# M-Fader.net
KiCad netlist of a schematic drawn in EAGLE
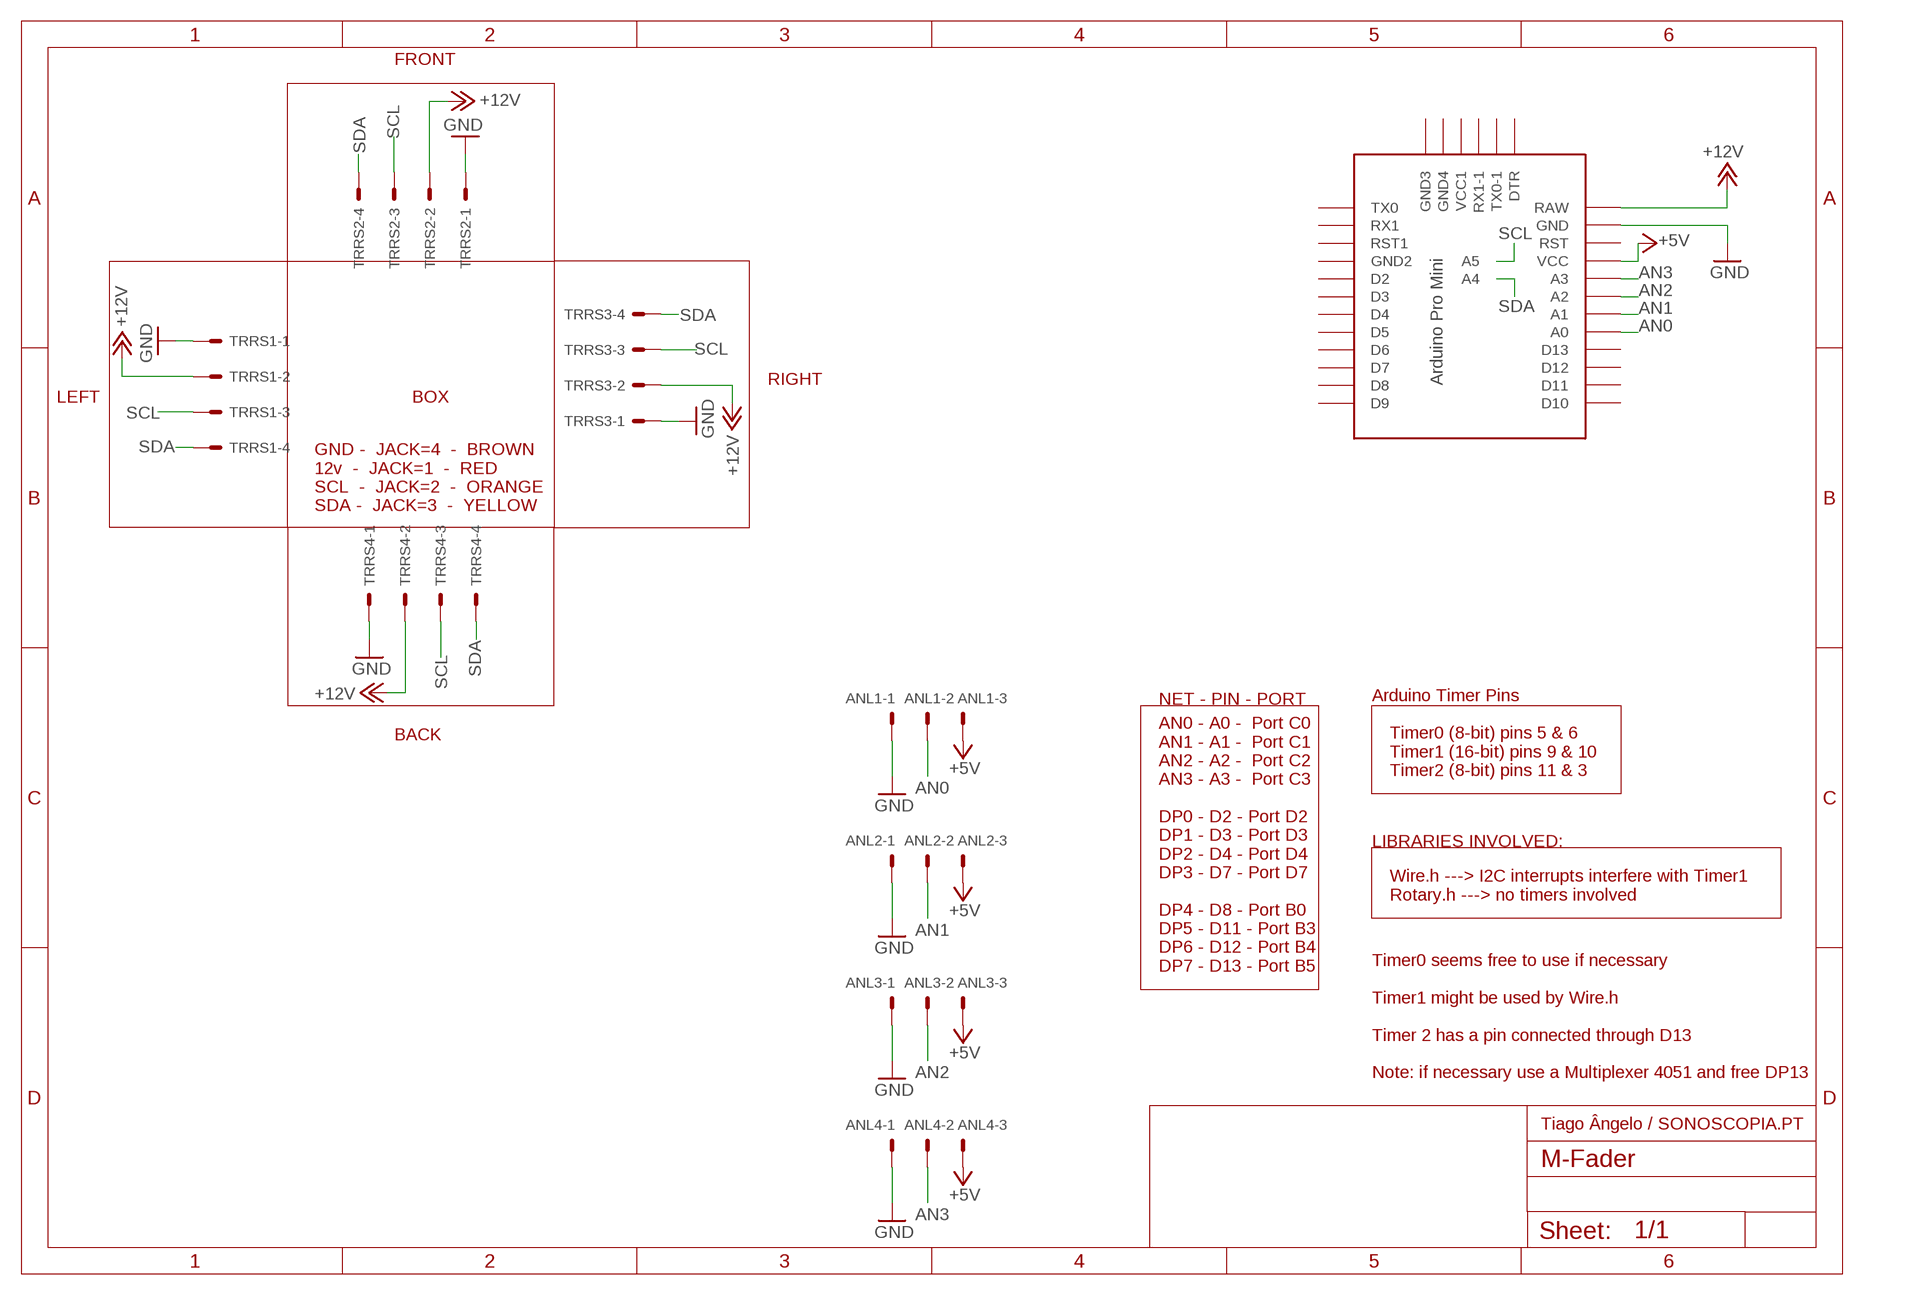
[diagram p0: schematic, sheet 1]

(export (version "E")
  (design (tool "Eeschema 10.0.6"))
  (components
    (comp (ref "ANL1")
      (value "22-27-2031-03")
      (footprint "eagle-import:6410-03")
      (libsource (lib "eagle-import") (part "22-?-0327-2031"))
    )
    (comp (ref "ANL2")
      (value "22-27-2031-03")
      (footprint "eagle-import:6410-03")
      (libsource (lib "eagle-import") (part "22-?-0327-2031"))
    )
    (comp (ref "ANL3")
      (value "22-27-2031-03")
      (footprint "eagle-import:6410-03")
      (libsource (lib "eagle-import") (part "22-?-0327-2031"))
    )
    (comp (ref "ANL4")
      (value "22-27-2031-03")
      (footprint "eagle-import:6410-03")
      (libsource (lib "eagle-import") (part "22-?-0327-2031"))
    )
    (comp (ref "TRRS1")
      (value "22-27-2041-04")
      (footprint "eagle-import:6410-04")
      (libsource (lib "eagle-import") (part "22-?-0427-2041"))
    )
    (comp (ref "TRRS2")
      (value "22-27-2041-04")
      (footprint "eagle-import:6410-04")
      (libsource (lib "eagle-import") (part "22-?-0427-2041"))
    )
    (comp (ref "TRRS3")
      (value "22-27-2041-04")
      (footprint "eagle-import:6410-04")
      (libsource (lib "eagle-import") (part "22-?-0427-2041"))
    )
    (comp (ref "TRRS4")
      (value "22-27-2041-04")
      (footprint "eagle-import:6410-04")
      (libsource (lib "eagle-import") (part "22-?-0427-2041"))
    )
    (comp (ref "U$1")
      (value "PRO-MINI-2")
      (footprint "eagle-import:PRO-MINI-2")
      (libsource (lib "eagle-import") (part "PRO-MINI-2"))
    )
  )
  (nets
    (net (code "1") (name "+5V") (class "Default")
      (node (ref "ANL1") (pin "3") (pinfunction "S_3") (pintype "passive"))
      (node (ref "ANL2") (pin "3") (pinfunction "S_3") (pintype "passive"))
      (node (ref "ANL3") (pin "3") (pinfunction "S_3") (pintype "passive"))
      (node (ref "ANL4") (pin "3") (pinfunction "S_3") (pintype "passive"))
      (node (ref "U$1") (pin "VCC") (pinfunction "VCC_VCC") (pintype "bidirectional"))
    )
    (net (code "2") (name "+12V") (class "Default")
      (node (ref "TRRS1") (pin "2") (pinfunction "S_2") (pintype "passive"))
      (node (ref "TRRS2") (pin "2") (pinfunction "S_2") (pintype "passive"))
      (node (ref "TRRS3") (pin "2") (pinfunction "S_2") (pintype "passive"))
      (node (ref "TRRS4") (pin "2") (pinfunction "S_2") (pintype "passive"))
      (node (ref "U$1") (pin "RAW") (pinfunction "RAW_RAW") (pintype "bidirectional"))
    )
    (net (code "3") (name "/AN0") (class "Default")
      (node (ref "ANL1") (pin "2") (pinfunction "S_2") (pintype "passive"))
      (node (ref "U$1") (pin "A0") (pinfunction "A0_A0") (pintype "bidirectional"))
    )
    (net (code "4") (name "/AN1") (class "Default")
      (node (ref "ANL2") (pin "2") (pinfunction "S_2") (pintype "passive"))
      (node (ref "U$1") (pin "A1") (pinfunction "A1_A1") (pintype "bidirectional"))
    )
    (net (code "5") (name "/AN2") (class "Default")
      (node (ref "ANL3") (pin "2") (pinfunction "S_2") (pintype "passive"))
      (node (ref "U$1") (pin "A2") (pinfunction "A2_A2") (pintype "bidirectional"))
    )
    (net (code "6") (name "/AN3") (class "Default")
      (node (ref "ANL4") (pin "2") (pinfunction "S_2") (pintype "passive"))
      (node (ref "U$1") (pin "A3") (pinfunction "A3_A3") (pintype "bidirectional"))
    )
    (net (code "7") (name "/SCL") (class "Default")
      (node (ref "TRRS1") (pin "3") (pinfunction "S_3") (pintype "passive"))
      (node (ref "TRRS2") (pin "3") (pinfunction "S_3") (pintype "passive"))
      (node (ref "TRRS3") (pin "3") (pinfunction "S_3") (pintype "passive"))
      (node (ref "TRRS4") (pin "3") (pinfunction "S_3") (pintype "passive"))
      (node (ref "U$1") (pin "A5") (pinfunction "A5_A5") (pintype "bidirectional"))
    )
    (net (code "8") (name "/SDA") (class "Default")
      (node (ref "TRRS1") (pin "4") (pinfunction "S_4") (pintype "passive"))
      (node (ref "TRRS2") (pin "4") (pinfunction "S_4") (pintype "passive"))
      (node (ref "TRRS3") (pin "4") (pinfunction "S_4") (pintype "passive"))
      (node (ref "TRRS4") (pin "4") (pinfunction "S_4") (pintype "passive"))
      (node (ref "U$1") (pin "A4") (pinfunction "A4_A4") (pintype "bidirectional"))
    )
    (net (code "9") (name "GND") (class "Default")
      (node (ref "ANL1") (pin "1") (pinfunction "S_1") (pintype "passive"))
      (node (ref "ANL2") (pin "1") (pinfunction "S_1") (pintype "passive"))
      (node (ref "ANL3") (pin "1") (pinfunction "S_1") (pintype "passive"))
      (node (ref "ANL4") (pin "1") (pinfunction "S_1") (pintype "passive"))
      (node (ref "TRRS1") (pin "1") (pinfunction "S_1") (pintype "passive"))
      (node (ref "TRRS2") (pin "1") (pinfunction "S_1") (pintype "passive"))
      (node (ref "TRRS3") (pin "1") (pinfunction "S_1") (pintype "passive"))
      (node (ref "TRRS4") (pin "1") (pinfunction "S_1") (pintype "passive"))
      (node (ref "U$1") (pin "GND") (pinfunction "GND_GND") (pintype "bidirectional"))
    )
    (net (code "10") (name "unconnected-(U$1-GND2-PadGND1)") (class "Default")
      (node (ref "U$1") (pin "GND1") (pinfunction "GND2_GND1") (pintype "bidirectional"))
    )
    (net (code "11") (name "unconnected-(U$1-GND3-PadGND2)") (class "Default")
      (node (ref "U$1") (pin "GND2") (pinfunction "GND3_GND2") (pintype "bidirectional"))
    )
    (net (code "12") (name "unconnected-(U$1-GND4-PadGND3)") (class "Default")
      (node (ref "U$1") (pin "GND3") (pinfunction "GND4_GND3") (pintype "bidirectional"))
    )
    (net (code "13") (name "unconnected-(U$1-PadD2)") (class "Default")
      (node (ref "U$1") (pin "D2") (pinfunction "D2_D2") (pintype "bidirectional"))
    )
    (net (code "14") (name "unconnected-(U$1-PadD3)") (class "Default")
      (node (ref "U$1") (pin "D3") (pinfunction "D3_D3") (pintype "bidirectional"))
    )
    (net (code "15") (name "unconnected-(U$1-PadD4)") (class "Default")
      (node (ref "U$1") (pin "D4") (pinfunction "D4_D4") (pintype "bidirectional"))
    )
    (net (code "16") (name "unconnected-(U$1-PadD5)") (class "Default")
      (node (ref "U$1") (pin "D5") (pinfunction "D5_D5") (pintype "bidirectional"))
    )
    (net (code "17") (name "unconnected-(U$1-PadD6)") (class "Default")
      (node (ref "U$1") (pin "D6") (pinfunction "D6_D6") (pintype "bidirectional"))
    )
    (net (code "18") (name "unconnected-(U$1-PadD7)") (class "Default")
      (node (ref "U$1") (pin "D7") (pinfunction "D7_D7") (pintype "bidirectional"))
    )
    (net (code "19") (name "unconnected-(U$1-PadD8)") (class "Default")
      (node (ref "U$1") (pin "D8") (pinfunction "D8_D8") (pintype "bidirectional"))
    )
    (net (code "20") (name "unconnected-(U$1-PadD9)") (class "Default")
      (node (ref "U$1") (pin "D9") (pinfunction "D9_D9") (pintype "bidirectional"))
    )
    (net (code "21") (name "unconnected-(U$1-PadD10)") (class "Default")
      (node (ref "U$1") (pin "D10") (pinfunction "D10_D10") (pintype "bidirectional"))
    )
    (net (code "22") (name "unconnected-(U$1-PadD11)") (class "Default")
      (node (ref "U$1") (pin "D11") (pinfunction "D11_D11") (pintype "bidirectional"))
    )
    (net (code "23") (name "unconnected-(U$1-PadD12)") (class "Default")
      (node (ref "U$1") (pin "D12") (pinfunction "D12_D12") (pintype "bidirectional"))
    )
    (net (code "24") (name "unconnected-(U$1-PadD13)") (class "Default")
      (node (ref "U$1") (pin "D13") (pinfunction "D13_D13") (pintype "bidirectional"))
    )
    (net (code "25") (name "unconnected-(U$1-PadDTR)") (class "Default")
      (node (ref "U$1") (pin "DTR") (pinfunction "DTR_DTR") (pintype "bidirectional"))
    )
    (net (code "26") (name "unconnected-(U$1-PadRST)") (class "Default")
      (node (ref "U$1") (pin "RST") (pinfunction "RST_RST") (pintype "bidirectional"))
    )
    (net (code "27") (name "unconnected-(U$1-PadRST1)") (class "Default")
      (node (ref "U$1") (pin "RST1") (pinfunction "RST1_RST1") (pintype "bidirectional"))
    )
    (net (code "28") (name "unconnected-(U$1-PadRX1)") (class "Default")
      (node (ref "U$1") (pin "RX1") (pinfunction "RX1_RX1") (pintype "bidirectional"))
    )
    (net (code "29") (name "unconnected-(U$1-PadRX1-1)") (class "Default")
      (node (ref "U$1") (pin "RX1-1") (pinfunction "RX1-1_RX1-1") (pintype "bidirectional"))
    )
    (net (code "30") (name "unconnected-(U$1-PadTX0)") (class "Default")
      (node (ref "U$1") (pin "TX0") (pinfunction "TX0_TX0") (pintype "bidirectional"))
    )
    (net (code "31") (name "unconnected-(U$1-PadTX0-1)") (class "Default")
      (node (ref "U$1") (pin "TX0-1") (pinfunction "TX0-1_TX0-1") (pintype "bidirectional"))
    )
    (net (code "32") (name "unconnected-(U$1-PadVCC1)") (class "Default")
      (node (ref "U$1") (pin "VCC1") (pinfunction "VCC1_VCC1") (pintype "bidirectional"))
    )
  )
)
